# GAT562_Mesh_Solar_Relay_V1_3.net
KiCad netlist of a schematic drawn in Altium Designer
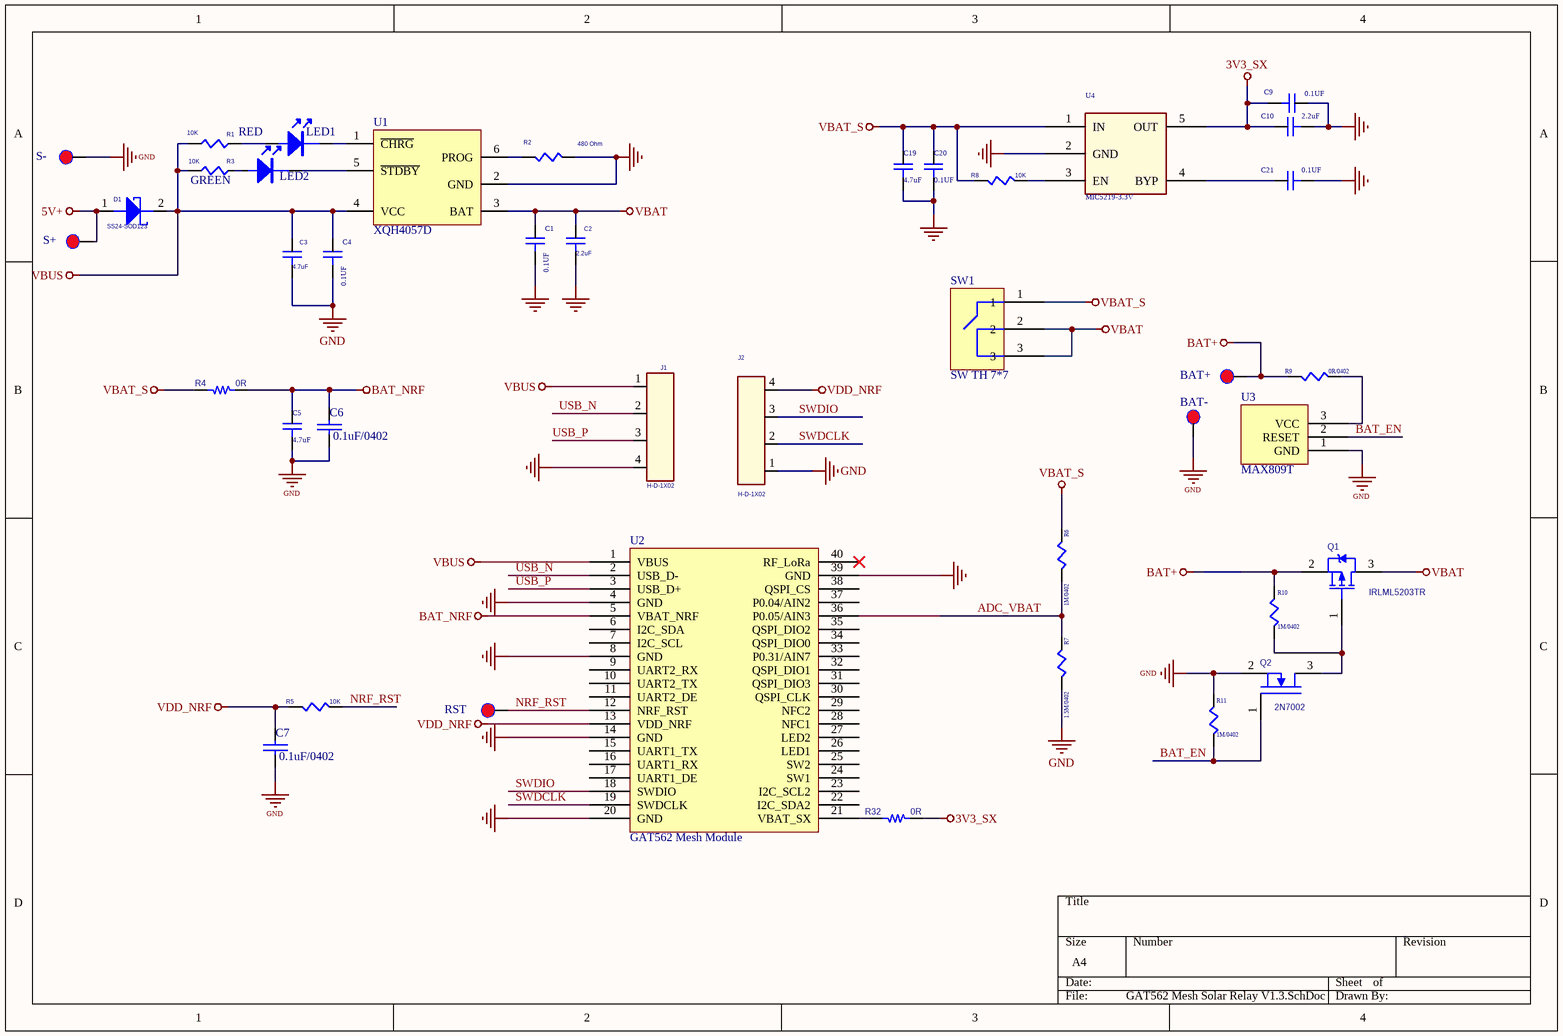
[diagram p0: GAT562 Mesh Solar Relay V1.3.SchDoc]

(export (version "E")
  (design (tool "Eeschema 10.0.6"))
  (components
    (comp (ref "BAT+")
      (value "~")
      (footprint "pad2*3")
      (libsource (lib "EasyARM-i.MX283-EV") (part "TEST-DOT"))
    )
    (comp (ref "BAT-")
      (value "~")
      (footprint "pad2*3")
      (libsource (lib "EasyARM-i.MX283-EV") (part "TEST-DOT"))
    )
    (comp (ref "C1") (value "0.1UF") (footprint "C0402") (libsource (lib "*") (part "0_1.1UF")))
    (comp (ref "C2") (value "2.2uF") (footprint "C0402") (libsource (lib "*") (part "0.1UF")))
    (comp (ref "C3") (value "4.7uF") (footprint "C0402") (libsource (lib "*") (part "0.1UF")))
    (comp (ref "C4") (value "0.1UF") (footprint "C0402") (libsource (lib "*") (part "0_1.1UF")))
    (comp (ref "C5") (value "4.7uF") (footprint "C0402") (libsource (lib "*") (part "0_1.1UF")))
    (comp (ref "C6")
      (value "0.1uF/0402")
      (footprint "C0402")
      (description "Capacitor")
      (libsource (lib "电阻容感类") (part "CAP"))
    )
    (comp (ref "C7")
      (value "0.1uF/0402")
      (footprint "C0402")
      (description "Capacitor")
      (libsource (lib "电阻容感类") (part "CAP"))
    )
    (comp (ref "C9") (value "0.1UF") (footprint "C0402") (libsource (lib "*") (part "0_1.1UF")))
    (comp (ref "C10") (value "2.2uF") (footprint "C0402") (libsource (lib "*") (part "0_1.1UF")))
    (comp (ref "C19") (value "4.7uF") (footprint "C0402") (libsource (lib "*") (part "0_1.1UF")))
    (comp (ref "C20") (value "0.1UF") (footprint "C0402") (libsource (lib "*") (part "0_1.1UF")))
    (comp (ref "C21") (value "0.1UF") (footprint "C0402") (libsource (lib "*") (part "0_1.1UF")))
    (comp (ref "D1")
      (value "SS24-SOD123")
      (footprint "SOD-123-1")
      (description "DIODE 1N5817,DIP, 20V, 1A")
      (libsource (lib "*") (part "DIODE SCHOTTKY_0"))
    )
    (comp (ref "J1") (value "H-D-1X02") (footprint "HDR1X4-2.0") (libsource (lib "*") (part "CON6_1_Dup1")))
    (comp (ref "J2") (value "H-D-1X02") (footprint "HDR1X4-2.0") (libsource (lib "") (part "CON6_1_Dup1_1")))
    (comp (ref "LED1")
      (value "RED")
      (footprint "LED0603_RED_3D")
      (libsource (lib "LoRa DTU_20180911") (part "LED"))
    )
    (comp (ref "LED2")
      (value "GREEN")
      (footprint "LED0603_RED_3D")
      (libsource (lib "LoRa DTU_20180911") (part "LED"))
    )
    (comp (ref "Q1")
      (value "IRLML5203TR")
      (footprint "SOT23")
      (description "P-Channel Power MOSFET")
      (fields (field (name "PUBLISHER") "Altium Limited"))
      (libsource (lib "EZ55WL_EKB") (part "PMOS-2"))
    )
    (comp (ref "Q2") (value "2N7002") (footprint "SOT23") (libsource (lib "EZ55WL_EKB") (part "MOSFET-N")))
    (comp (ref "R1") (value "10K") (footprint "R0402") (libsource (lib "*") (part "R0402_1.06K_WALSIN")))
    (comp (ref "R2") (value "480 Ohm") (footprint "R0402") (libsource (lib "*") (part "R0402_1.06K_WALSIN")))
    (comp (ref "R3") (value "10K") (footprint "R0402") (libsource (lib "*") (part "R0402_1.06K_WALSIN")))
    (comp (ref "R4")
      (value "0R")
      (footprint "R0402")
      (description "Resistor , 2K Ohm 0402  5%")
      (libsource (lib "AcSiP 2013") (part "RES"))
    )
    (comp (ref "R5") (value "10K") (footprint "R0402") (libsource (lib "*") (part "R0402_1.06K_WALSIN")))
    (comp (ref "R6") (value "1M/0402") (footprint "R0402") (libsource (lib "*") (part "R0402_1.06K_WALSIN")))
    (comp (ref "R7")
      (value "1.5M/0402")
      (footprint "R0402")
      (libsource (lib "*") (part "R0402_1.06K_WALSIN"))
    )
    (comp (ref "R8") (value "10K") (footprint "R0402") (libsource (lib "*") (part "R0402_1.06K_WALSIN")))
    (comp (ref "R9") (value "0R/0402") (footprint "R0402") (libsource (lib "*") (part "R0402_1.06K_WALSIN")))
    (comp (ref "R10") (value "1M/0402") (footprint "R0402") (libsource (lib "*") (part "R0402_1.06K_WALSIN")))
    (comp (ref "R11") (value "1M/0402") (footprint "R0402") (libsource (lib "*") (part "R0402_1.06K_WALSIN")))
    (comp (ref "R32")
      (value "0R")
      (footprint "R0402")
      (description "Resistor , 2K Ohm 0402  5%")
      (libsource (lib "AcSiP 2013") (part "RES"))
    )
    (comp (ref "RST")
      (value "~")
      (footprint "PAD_29mil")
      (libsource (lib "EasyARM-i.MX283-EV") (part "TEST-DOT"))
    )
    (comp (ref "S+")
      (value "~")
      (footprint "pad1*2")
      (libsource (lib "EasyARM-i.MX283-EV") (part "TEST-DOT"))
    )
    (comp (ref "S-")
      (value "~")
      (footprint "pad1*2")
      (libsource (lib "EasyARM-i.MX283-EV") (part "TEST-DOT"))
    )
    (comp (ref "SW1")
      (value "SW TH 7*7")
      (footprint "SW TH 7*7")
      (description "SW TH 7*7 3P/6P")
      (libsource (lib "ALL Schlib") (part "SW TH 7*7"))
    )
    (comp (ref "U1") (value "XQH4057D") (footprint "XQH4057D") (libsource (lib "DRT") (part "XQH4057D")))
    (comp (ref "U2")
      (value "GAT562 Mesh Module")
      (footprint "gat562 module")
      (libsource (lib "schlib") (part "INTERFACE"))
    )
    (comp (ref "U3")
      (value "MAX809T")
      (footprint "SOT23")
      (description "MAX809T SOT23")
      (libsource (lib "ALL Schlib") (part "MAX809T"))
    )
    (comp (ref "U4")
      (value "MIC5219-3.3V")
      (footprint "SOT23-5")
      (libsource (lib "*") (part "REG CAT7101_2"))
    )
  )
  (nets
    (net (code "1") (name "/ADC_VBAT") (class "Default")
      (node (ref "R6") (pin "1") (pinfunction "1_1") (pintype "passive"))
      (node (ref "R7") (pin "2") (pinfunction "2_2") (pintype "passive"))
      (node (ref "U2") (pin "36") (pinfunction "P0.05/AIN3_36") (pintype "passive"))
    )
    (net (code "2") (name "/BAT_EN") (class "Default")
      (node (ref "Q2") (pin "1") (pinfunction "IN_1") (pintype "passive"))
      (node (ref "R11") (pin "1") (pinfunction "1_1") (pintype "passive"))
      (node (ref "U3") (pin "2") (pinfunction "RESET_2") (pintype "passive"))
    )
    (net (code "3") (name "/NRF_RST") (class "Default")
      (node (ref "R5") (pin "2") (pinfunction "2_2") (pintype "passive"))
      (node (ref "RST") (pin "1") (pinfunction "1_1") (pintype "passive"))
      (node (ref "U2") (pin "12") (pinfunction "NRF_RST_12") (pintype "passive"))
    )
    (net (code "4") (name "/SWDCLK") (class "Default")
      (node (ref "J2") (pin "2") (pinfunction "2_2") (pintype "passive"))
      (node (ref "U2") (pin "19") (pinfunction "SWDCLK_19") (pintype "passive"))
    )
    (net (code "5") (name "/SWDIO") (class "Default")
      (node (ref "J2") (pin "3") (pinfunction "3_3") (pintype "passive"))
      (node (ref "U2") (pin "18") (pinfunction "SWDIO_18") (pintype "passive"))
    )
    (net (code "6") (name "/USB_N") (class "Default")
      (node (ref "J1") (pin "2") (pinfunction "2_2") (pintype "passive"))
      (node (ref "U2") (pin "2") (pinfunction "USB_D-_2") (pintype "passive"))
    )
    (net (code "7") (name "/USB_P") (class "Default")
      (node (ref "J1") (pin "3") (pinfunction "3_3") (pintype "passive"))
      (node (ref "U2") (pin "3") (pinfunction "USB_D+_3") (pintype "passive"))
    )
    (net (code "8") (name "3V3_SX") (class "Default")
      (node (ref "C10") (pin "1") (pinfunction "1_1") (pintype "passive"))
      (node (ref "C9") (pin "2") (pinfunction "2_2") (pintype "passive"))
      (node (ref "R32") (pin "2") (pinfunction "2_2") (pintype "passive"))
      (node (ref "U4") (pin "5") (pinfunction "OUT_5") (pintype "passive"))
    )
    (net (code "9") (name "5V+") (class "Default")
      (node (ref "D1") (pin "1") (pinfunction "ANODE_1") (pintype "passive"))
      (node (ref "S+") (pin "1") (pinfunction "1_1") (pintype "passive"))
    )
    (net (code "10") (name "BAT+") (class "Default")
      (node (ref "BAT+") (pin "1") (pinfunction "1_1") (pintype "passive"))
      (node (ref "Q1") (pin "2") (pinfunction "S_2") (pintype "passive"))
      (node (ref "R10") (pin "2") (pinfunction "2_2") (pintype "passive"))
      (node (ref "R9") (pin "2") (pinfunction "2_2") (pintype "passive"))
    )
    (net (code "11") (name "BAT_NRF") (class "Default")
      (node (ref "C5") (pin "1") (pinfunction "1_1") (pintype "passive"))
      (node (ref "C6") (pin "2") (pinfunction "2_2") (pintype "passive"))
      (node (ref "R4") (pin "2") (pinfunction "2_2") (pintype "passive"))
      (node (ref "U2") (pin "5") (pinfunction "VBAT_NRF_5") (pintype "passive"))
    )
    (net (code "12") (name "GND") (class "Default")
      (node (ref "BAT-") (pin "1") (pinfunction "1_1") (pintype "passive"))
      (node (ref "C1") (pin "2") (pinfunction "2_2") (pintype "passive"))
      (node (ref "C10") (pin "2") (pinfunction "2_2") (pintype "passive"))
      (node (ref "C19") (pin "2") (pinfunction "2_2") (pintype "passive"))
      (node (ref "C2") (pin "2") (pinfunction "2_2") (pintype "passive"))
      (node (ref "C20") (pin "2") (pinfunction "2_2") (pintype "passive"))
      (node (ref "C21") (pin "2") (pinfunction "2_2") (pintype "passive"))
      (node (ref "C3") (pin "2") (pinfunction "2_2") (pintype "passive"))
      (node (ref "C4") (pin "2") (pinfunction "2_2") (pintype "passive"))
      (node (ref "C5") (pin "2") (pinfunction "2_2") (pintype "passive"))
      (node (ref "C6") (pin "1") (pinfunction "1_1") (pintype "passive"))
      (node (ref "C7") (pin "1") (pinfunction "1_1") (pintype "passive"))
      (node (ref "C9") (pin "1") (pinfunction "1_1") (pintype "passive"))
      (node (ref "J1") (pin "4") (pinfunction "4_4") (pintype "passive"))
      (node (ref "J2") (pin "1") (pinfunction "1_1") (pintype "passive"))
      (node (ref "Q2") (pin "2") (pinfunction "OUT_2") (pintype "passive"))
      (node (ref "R11") (pin "2") (pinfunction "2_2") (pintype "passive"))
      (node (ref "R2") (pin "2") (pinfunction "2_2") (pintype "passive"))
      (node (ref "R7") (pin "1") (pinfunction "1_1") (pintype "passive"))
      (node (ref "S-") (pin "1") (pinfunction "1_1") (pintype "passive"))
      (node (ref "U1") (pin "2") (pinfunction "GND_2") (pintype "passive"))
      (node (ref "U2") (pin "14") (pinfunction "GND_14") (pintype "passive"))
      (node (ref "U2") (pin "20") (pinfunction "GND_20") (pintype "passive"))
      (node (ref "U2") (pin "39") (pinfunction "GND_39") (pintype "passive"))
      (node (ref "U2") (pin "4") (pinfunction "GND_4") (pintype "passive"))
      (node (ref "U2") (pin "8") (pinfunction "GND_8") (pintype "passive"))
      (node (ref "U3") (pin "1") (pinfunction "GND_1") (pintype "passive"))
      (node (ref "U4") (pin "2") (pinfunction "GND_2") (pintype "passive"))
    )
    (net (code "13") (name "Net-(LED1-Pad1)") (class "Default")
      (node (ref "LED1") (pin "1") (pinfunction "1_1") (pintype "passive"))
      (node (ref "R1") (pin "1") (pinfunction "1_1") (pintype "passive"))
    )
    (net (code "14") (name "Net-(LED2-Pad1)") (class "Default")
      (node (ref "LED2") (pin "1") (pinfunction "1_1") (pintype "passive"))
      (node (ref "R3") (pin "1") (pinfunction "1_1") (pintype "passive"))
    )
    (net (code "15") (name "Net-(Q1-G)") (class "Default")
      (node (ref "Q1") (pin "1") (pinfunction "G_1") (pintype "passive"))
      (node (ref "Q2") (pin "3") (pinfunction "GND_3") (pintype "passive"))
      (node (ref "R10") (pin "1") (pinfunction "1_1") (pintype "passive"))
    )
    (net (code "16") (name "Net-(U1-PROG)") (class "Default")
      (node (ref "R2") (pin "1") (pinfunction "1_1") (pintype "passive"))
      (node (ref "U1") (pin "6") (pinfunction "PROG_6") (pintype "passive"))
    )
    (net (code "17") (name "Net-(U1-~{CHRG})") (class "Default")
      (node (ref "LED1") (pin "2") (pinfunction "2_2") (pintype "passive"))
      (node (ref "U1") (pin "1") (pinfunction "~{CHRG}_1") (pintype "passive"))
    )
    (net (code "18") (name "Net-(U1-~{STDBY})") (class "Default")
      (node (ref "LED2") (pin "2") (pinfunction "2_2") (pintype "passive"))
      (node (ref "U1") (pin "5") (pinfunction "~{STDBY}_5") (pintype "passive"))
    )
    (net (code "19") (name "Net-(U2-VBAT_SX)") (class "Default")
      (node (ref "R32") (pin "1") (pinfunction "1_1") (pintype "passive"))
      (node (ref "U2") (pin "21") (pinfunction "VBAT_SX_21") (pintype "passive"))
    )
    (net (code "20") (name "Net-(U3-VCC)") (class "Default")
      (node (ref "R9") (pin "1") (pinfunction "1_1") (pintype "passive"))
      (node (ref "U3") (pin "3") (pinfunction "VCC_3") (pintype "passive"))
    )
    (net (code "21") (name "Net-(U4-BYP)") (class "Default")
      (node (ref "C21") (pin "1") (pinfunction "1_1") (pintype "passive"))
      (node (ref "U4") (pin "4") (pinfunction "BYP_4") (pintype "passive"))
    )
    (net (code "22") (name "Net-(U4-EN)") (class "Default")
      (node (ref "R8") (pin "2") (pinfunction "2_2") (pintype "passive"))
      (node (ref "U4") (pin "3") (pinfunction "EN_3") (pintype "passive"))
    )
    (net (code "23") (name "VBAT") (class "Default")
      (node (ref "C1") (pin "1") (pinfunction "1_1") (pintype "passive"))
      (node (ref "C2") (pin "1") (pinfunction "1_1") (pintype "passive"))
      (node (ref "Q1") (pin "3") (pinfunction "D_3") (pintype "passive"))
      (node (ref "SW1") (pin "2") (pinfunction "_2_2") (pintype "passive"))
      (node (ref "SW1") (pin "3") (pinfunction "3_3") (pintype "passive"))
      (node (ref "U1") (pin "3") (pinfunction "BAT_3") (pintype "passive"))
    )
    (net (code "24") (name "VBAT_S") (class "Default")
      (node (ref "C19") (pin "1") (pinfunction "1_1") (pintype "passive"))
      (node (ref "C20") (pin "1") (pinfunction "1_1") (pintype "passive"))
      (node (ref "R4") (pin "1") (pinfunction "1_1") (pintype "passive"))
      (node (ref "R6") (pin "2") (pinfunction "2_2") (pintype "passive"))
      (node (ref "R8") (pin "1") (pinfunction "1_1") (pintype "passive"))
      (node (ref "SW1") (pin "1") (pinfunction "1_1") (pintype "passive"))
      (node (ref "U4") (pin "1") (pinfunction "IN_1") (pintype "passive"))
    )
    (net (code "25") (name "VBUS") (class "Default")
      (node (ref "C3") (pin "1") (pinfunction "1_1") (pintype "passive"))
      (node (ref "C4") (pin "1") (pinfunction "1_1") (pintype "passive"))
      (node (ref "D1") (pin "2") (pinfunction "CATHODE_2") (pintype "passive"))
      (node (ref "J1") (pin "1") (pinfunction "1_1") (pintype "passive"))
      (node (ref "R1") (pin "2") (pinfunction "2_2") (pintype "passive"))
      (node (ref "R3") (pin "2") (pinfunction "2_2") (pintype "passive"))
      (node (ref "U1") (pin "4") (pinfunction "VCC_4") (pintype "passive"))
      (node (ref "U2") (pin "1") (pinfunction "VBUS_1") (pintype "passive"))
    )
    (net (code "26") (name "VDD_NRF") (class "Default")
      (node (ref "C7") (pin "2") (pinfunction "2_2") (pintype "passive"))
      (node (ref "J2") (pin "4") (pinfunction "4_4") (pintype "passive"))
      (node (ref "R5") (pin "1") (pinfunction "1_1") (pintype "passive"))
      (node (ref "U2") (pin "13") (pinfunction "VDD_NRF_13") (pintype "passive"))
    )
    (net (code "27") (name "unconnected-(U2-I2C_SCL-Pad7)") (class "Default")
      (node (ref "U2") (pin "7") (pinfunction "I2C_SCL_7") (pintype "passive"))
    )
    (net (code "28") (name "unconnected-(U2-I2C_SCL2-Pad23)") (class "Default")
      (node (ref "U2") (pin "23") (pinfunction "I2C_SCL2_23") (pintype "passive"))
    )
    (net (code "29") (name "unconnected-(U2-I2C_SDA-Pad6)") (class "Default")
      (node (ref "U2") (pin "6") (pinfunction "I2C_SDA_6") (pintype "passive"))
    )
    (net (code "30") (name "unconnected-(U2-I2C_SDA2-Pad22)") (class "Default")
      (node (ref "U2") (pin "22") (pinfunction "I2C_SDA2_22") (pintype "passive"))
    )
    (net (code "31") (name "unconnected-(U2-LED1-Pad26)") (class "Default")
      (node (ref "U2") (pin "26") (pinfunction "LED1_26") (pintype "passive"))
    )
    (net (code "32") (name "unconnected-(U2-LED2-Pad27)") (class "Default")
      (node (ref "U2") (pin "27") (pinfunction "LED2_27") (pintype "passive"))
    )
    (net (code "33") (name "unconnected-(U2-NFC1-Pad28)") (class "Default")
      (node (ref "U2") (pin "28") (pinfunction "NFC1_28") (pintype "passive"))
    )
    (net (code "34") (name "unconnected-(U2-NFC2-Pad29)") (class "Default")
      (node (ref "U2") (pin "29") (pinfunction "NFC2_29") (pintype "passive"))
    )
    (net (code "35") (name "unconnected-(U2-P0.04{slash}AIN2-Pad37)") (class "Default")
      (node (ref "U2") (pin "37") (pinfunction "P0.04/AIN2_37") (pintype "passive"))
    )
    (net (code "36") (name "unconnected-(U2-P0.31{slash}AIN7-Pad33)") (class "Default")
      (node (ref "U2") (pin "33") (pinfunction "P0.31/AIN7_33") (pintype "passive"))
    )
    (net (code "37") (name "unconnected-(U2-QSPI_CLK-Pad30)") (class "Default")
      (node (ref "U2") (pin "30") (pinfunction "QSPI_CLK_30") (pintype "passive"))
    )
    (net (code "38") (name "unconnected-(U2-QSPI_CS-Pad38)") (class "Default")
      (node (ref "U2") (pin "38") (pinfunction "QSPI_CS_38") (pintype "passive"))
    )
    (net (code "39") (name "unconnected-(U2-QSPI_DIO0-Pad34)") (class "Default")
      (node (ref "U2") (pin "34") (pinfunction "QSPI_DIO0_34") (pintype "passive"))
    )
    (net (code "40") (name "unconnected-(U2-QSPI_DIO1-Pad32)") (class "Default")
      (node (ref "U2") (pin "32") (pinfunction "QSPI_DIO1_32") (pintype "passive"))
    )
    (net (code "41") (name "unconnected-(U2-QSPI_DIO2-Pad35)") (class "Default")
      (node (ref "U2") (pin "35") (pinfunction "QSPI_DIO2_35") (pintype "passive"))
    )
    (net (code "42") (name "unconnected-(U2-QSPI_DIO3-Pad31)") (class "Default")
      (node (ref "U2") (pin "31") (pinfunction "QSPI_DIO3_31") (pintype "passive"))
    )
    (net (code "43") (name "unconnected-(U2-RF_LoRa-Pad40)") (class "Default")
      (node (ref "U2") (pin "40") (pinfunction "RF_LoRa_40") (pintype "passive+no_connect"))
    )
    (net (code "44") (name "unconnected-(U2-SW1-Pad24)") (class "Default")
      (node (ref "U2") (pin "24") (pinfunction "SW1_24") (pintype "passive"))
    )
    (net (code "45") (name "unconnected-(U2-SW2-Pad25)") (class "Default")
      (node (ref "U2") (pin "25") (pinfunction "SW2_25") (pintype "passive"))
    )
    (net (code "46") (name "unconnected-(U2-UART1_DE-Pad17)") (class "Default")
      (node (ref "U2") (pin "17") (pinfunction "UART1_DE_17") (pintype "passive"))
    )
    (net (code "47") (name "unconnected-(U2-UART1_RX-Pad16)") (class "Default")
      (node (ref "U2") (pin "16") (pinfunction "UART1_RX_16") (pintype "passive"))
    )
    (net (code "48") (name "unconnected-(U2-UART1_TX-Pad15)") (class "Default")
      (node (ref "U2") (pin "15") (pinfunction "UART1_TX_15") (pintype "passive"))
    )
    (net (code "49") (name "unconnected-(U2-UART2_DE-Pad11)") (class "Default")
      (node (ref "U2") (pin "11") (pinfunction "UART2_DE_11") (pintype "passive"))
    )
    (net (code "50") (name "unconnected-(U2-UART2_RX-Pad9)") (class "Default")
      (node (ref "U2") (pin "9") (pinfunction "UART2_RX_9") (pintype "passive"))
    )
    (net (code "51") (name "unconnected-(U2-UART2_TX-Pad10)") (class "Default")
      (node (ref "U2") (pin "10") (pinfunction "UART2_TX_10") (pintype "passive"))
    )
  )
)
